# Schema2_bakplan_Lynx.net
KiCad netlist of a schematic drawn in Altium Designer
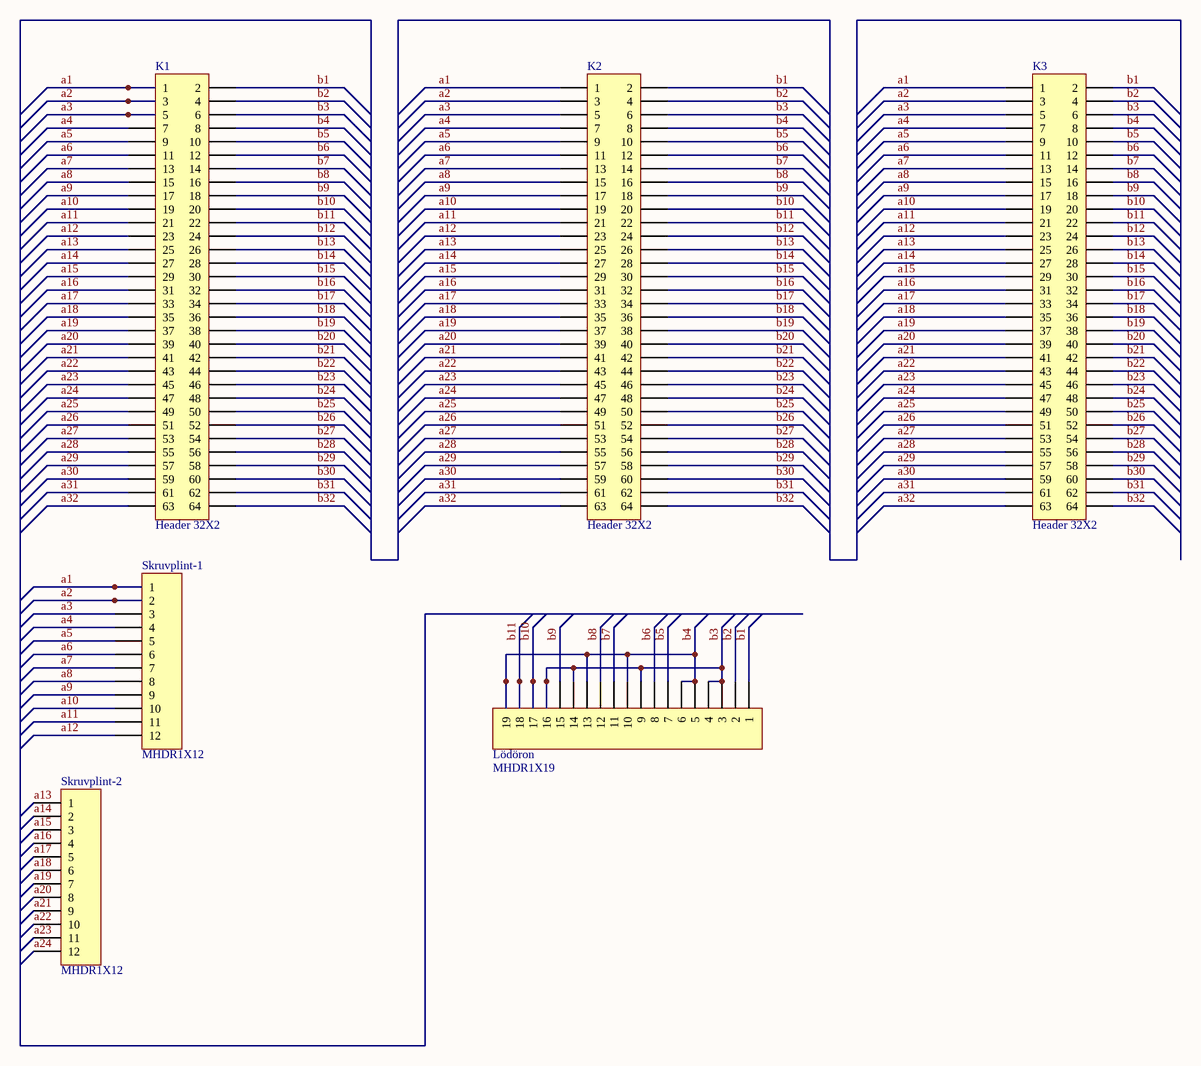
[diagram p0: Schema2_bakplan_Lynx.SchDoc]

(export (version "E")
  (design (tool "Eeschema 10.0.6"))
  (components
    (comp (ref "K1")
      (value "Header 32X2")
      (footprint "DIN41612_EuropadonB64_Hyls")
      (description "Header, 30-Pin, Dual row")
      (fields (field (name "MANUFACTURER") "Generic Components") (field (name "PUBLISHER") "Altium Limited"))
      (libsource (lib "Bakplan_Lynx") (part "Header 30X2"))
    )
    (comp (ref "K2")
      (value "Header 32X2")
      (footprint "DIN41612_EuropadonB64_Hyls")
      (description "Header, 30-Pin, Dual row")
      (fields (field (name "MANUFACTURER") "Generic Components") (field (name "PUBLISHER") "Altium Limited"))
      (libsource (lib "Bakplan_Lynx") (part "Header 30X2"))
    )
    (comp (ref "K3")
      (value "Header 32X2")
      (footprint "DIN41612_EuropadonB64_Hyls")
      (description "Header, 30-Pin, Dual row")
      (fields (field (name "MANUFACTURER") "Generic Components") (field (name "PUBLISHER") "Altium Limited"))
      (libsource (lib "Bakplan_Lynx") (part "Header 30X2"))
    )
    (comp (ref "Lödöron")
      (value "MHDR1X19")
      (footprint "Lödöron_19:Lödöron_19")
      (description "Header, 19-Pin")
      (fields (field (name "MANUFACTURER") "Generic Components") (field (name "PUBLISHER") "Altium Limited"))
      (libsource (lib "Miscellaneous Connectors") (part "MHDR1X19"))
    )
    (comp (ref "Skruvplint-1")
      (value "MHDR1X12")
      (footprint "Plint12:Plint12")
      (description "Header, 12-Pin")
      (fields (field (name "MANUFACTURER") "Generic Components") (field (name "PUBLISHER") "Altium Limited"))
      (libsource (lib "Bakplan_Lynx") (part "MHDR1X12"))
    )
    (comp (ref "Skruvplint-2")
      (value "MHDR1X12")
      (footprint "Plint12:Plint12")
      (description "Header, 12-Pin")
      (fields (field (name "MANUFACTURER") "Generic Components") (field (name "PUBLISHER") "Altium Limited"))
      (libsource (lib "Bakplan_Lynx") (part "MHDR1X12"))
    )
  )
  (nets
    (net (code "1") (name "/a1") (class "Default")
      (node (ref "K1") (pin "1") (pinfunction "1_1") (pintype "passive"))
      (node (ref "K2") (pin "1") (pinfunction "1_1") (pintype "passive"))
      (node (ref "K3") (pin "1") (pinfunction "1_1") (pintype "passive"))
      (node (ref "Skruvplint-1") (pin "1") (pinfunction "1_1") (pintype "passive"))
    )
    (net (code "2") (name "/a2") (class "Default")
      (node (ref "K1") (pin "3") (pinfunction "3_3") (pintype "passive"))
      (node (ref "K2") (pin "3") (pinfunction "3_3") (pintype "passive"))
      (node (ref "K3") (pin "3") (pinfunction "3_3") (pintype "passive"))
      (node (ref "Skruvplint-1") (pin "2") (pinfunction "2_2") (pintype "passive"))
    )
    (net (code "3") (name "/a3") (class "Default")
      (node (ref "K1") (pin "5") (pinfunction "5_5") (pintype "passive"))
      (node (ref "K2") (pin "5") (pinfunction "5_5") (pintype "passive"))
      (node (ref "K3") (pin "5") (pinfunction "5_5") (pintype "passive"))
      (node (ref "Skruvplint-1") (pin "3") (pinfunction "3_3") (pintype "passive"))
    )
    (net (code "4") (name "/a4") (class "Default")
      (node (ref "K1") (pin "7") (pinfunction "7_7") (pintype "passive"))
      (node (ref "K2") (pin "7") (pinfunction "7_7") (pintype "passive"))
      (node (ref "K3") (pin "7") (pinfunction "7_7") (pintype "passive"))
      (node (ref "Skruvplint-1") (pin "4") (pinfunction "4_4") (pintype "passive"))
    )
    (net (code "5") (name "/a5") (class "Default")
      (node (ref "K1") (pin "9") (pinfunction "9_9") (pintype "passive"))
      (node (ref "K2") (pin "9") (pinfunction "9_9") (pintype "passive"))
      (node (ref "K3") (pin "9") (pinfunction "9_9") (pintype "passive"))
      (node (ref "Skruvplint-1") (pin "5") (pinfunction "5_5") (pintype "passive"))
    )
    (net (code "6") (name "/a6") (class "Default")
      (node (ref "K1") (pin "11") (pinfunction "11_11") (pintype "passive"))
      (node (ref "K2") (pin "11") (pinfunction "11_11") (pintype "passive"))
      (node (ref "K3") (pin "11") (pinfunction "11_11") (pintype "passive"))
      (node (ref "Skruvplint-1") (pin "6") (pinfunction "6_6") (pintype "passive"))
    )
    (net (code "7") (name "/a7") (class "Default")
      (node (ref "K1") (pin "13") (pinfunction "13_13") (pintype "passive"))
      (node (ref "K2") (pin "13") (pinfunction "13_13") (pintype "passive"))
      (node (ref "K3") (pin "13") (pinfunction "13_13") (pintype "passive"))
      (node (ref "Skruvplint-1") (pin "7") (pinfunction "7_7") (pintype "passive"))
    )
    (net (code "8") (name "/a8") (class "Default")
      (node (ref "K1") (pin "15") (pinfunction "15_15") (pintype "passive"))
      (node (ref "K2") (pin "15") (pinfunction "15_15") (pintype "passive"))
      (node (ref "K3") (pin "15") (pinfunction "15_15") (pintype "passive"))
      (node (ref "Skruvplint-1") (pin "8") (pinfunction "8_8") (pintype "passive"))
    )
    (net (code "9") (name "/a9") (class "Default")
      (node (ref "K1") (pin "17") (pinfunction "17_17") (pintype "passive"))
      (node (ref "K2") (pin "17") (pinfunction "17_17") (pintype "passive"))
      (node (ref "K3") (pin "17") (pinfunction "17_17") (pintype "passive"))
      (node (ref "Skruvplint-1") (pin "9") (pinfunction "9_9") (pintype "passive"))
    )
    (net (code "10") (name "/a10") (class "Default")
      (node (ref "K1") (pin "19") (pinfunction "19_19") (pintype "passive"))
      (node (ref "K2") (pin "19") (pinfunction "19_19") (pintype "passive"))
      (node (ref "K3") (pin "19") (pinfunction "19_19") (pintype "passive"))
      (node (ref "Skruvplint-1") (pin "10") (pinfunction "10_10") (pintype "passive"))
    )
    (net (code "11") (name "/a11") (class "Default")
      (node (ref "K1") (pin "21") (pinfunction "21_21") (pintype "passive"))
      (node (ref "K2") (pin "21") (pinfunction "21_21") (pintype "passive"))
      (node (ref "K3") (pin "21") (pinfunction "21_21") (pintype "passive"))
      (node (ref "Skruvplint-1") (pin "11") (pinfunction "11_11") (pintype "passive"))
    )
    (net (code "12") (name "/a12") (class "Default")
      (node (ref "K1") (pin "23") (pinfunction "23_23") (pintype "passive"))
      (node (ref "K2") (pin "23") (pinfunction "23_23") (pintype "passive"))
      (node (ref "K3") (pin "23") (pinfunction "23_23") (pintype "passive"))
      (node (ref "Skruvplint-1") (pin "12") (pinfunction "12_12") (pintype "passive"))
    )
    (net (code "13") (name "/a13") (class "Default")
      (node (ref "K1") (pin "25") (pinfunction "25_25") (pintype "passive"))
      (node (ref "K2") (pin "25") (pinfunction "25_25") (pintype "passive"))
      (node (ref "K3") (pin "25") (pinfunction "25_25") (pintype "passive"))
      (node (ref "Skruvplint-2") (pin "1") (pinfunction "1_1") (pintype "passive"))
    )
    (net (code "14") (name "/a14") (class "Default")
      (node (ref "K1") (pin "27") (pinfunction "27_27") (pintype "passive"))
      (node (ref "K2") (pin "27") (pinfunction "27_27") (pintype "passive"))
      (node (ref "K3") (pin "27") (pinfunction "27_27") (pintype "passive"))
      (node (ref "Skruvplint-2") (pin "2") (pinfunction "2_2") (pintype "passive"))
    )
    (net (code "15") (name "/a15") (class "Default")
      (node (ref "K1") (pin "29") (pinfunction "29_29") (pintype "passive"))
      (node (ref "K2") (pin "29") (pinfunction "29_29") (pintype "passive"))
      (node (ref "K3") (pin "29") (pinfunction "29_29") (pintype "passive"))
      (node (ref "Skruvplint-2") (pin "3") (pinfunction "3_3") (pintype "passive"))
    )
    (net (code "16") (name "/a16") (class "Default")
      (node (ref "K1") (pin "31") (pinfunction "31_31") (pintype "passive"))
      (node (ref "K2") (pin "31") (pinfunction "31_31") (pintype "passive"))
      (node (ref "K3") (pin "31") (pinfunction "31_31") (pintype "passive"))
      (node (ref "Skruvplint-2") (pin "4") (pinfunction "4_4") (pintype "passive"))
    )
    (net (code "17") (name "/a17") (class "Default")
      (node (ref "K1") (pin "33") (pinfunction "33_33") (pintype "passive"))
      (node (ref "K2") (pin "33") (pinfunction "33_33") (pintype "passive"))
      (node (ref "K3") (pin "33") (pinfunction "33_33") (pintype "passive"))
      (node (ref "Skruvplint-2") (pin "5") (pinfunction "5_5") (pintype "passive"))
    )
    (net (code "18") (name "/a18") (class "Default")
      (node (ref "K1") (pin "35") (pinfunction "35_35") (pintype "passive"))
      (node (ref "K2") (pin "35") (pinfunction "35_35") (pintype "passive"))
      (node (ref "K3") (pin "35") (pinfunction "35_35") (pintype "passive"))
      (node (ref "Skruvplint-2") (pin "6") (pinfunction "6_6") (pintype "passive"))
    )
    (net (code "19") (name "/a19") (class "Default")
      (node (ref "K1") (pin "37") (pinfunction "37_37") (pintype "passive"))
      (node (ref "K2") (pin "37") (pinfunction "37_37") (pintype "passive"))
      (node (ref "K3") (pin "37") (pinfunction "37_37") (pintype "passive"))
      (node (ref "Skruvplint-2") (pin "7") (pinfunction "7_7") (pintype "passive"))
    )
    (net (code "20") (name "/a20") (class "Default")
      (node (ref "K1") (pin "39") (pinfunction "39_39") (pintype "passive"))
      (node (ref "K2") (pin "39") (pinfunction "39_39") (pintype "passive"))
      (node (ref "K3") (pin "39") (pinfunction "39_39") (pintype "passive"))
      (node (ref "Skruvplint-2") (pin "8") (pinfunction "8_8") (pintype "passive"))
    )
    (net (code "21") (name "/a21") (class "Default")
      (node (ref "K1") (pin "41") (pinfunction "41_41") (pintype "passive"))
      (node (ref "K2") (pin "41") (pinfunction "41_41") (pintype "passive"))
      (node (ref "K3") (pin "41") (pinfunction "41_41") (pintype "passive"))
      (node (ref "Skruvplint-2") (pin "9") (pinfunction "9_9") (pintype "passive"))
    )
    (net (code "22") (name "/a22") (class "Default")
      (node (ref "K1") (pin "43") (pinfunction "43_43") (pintype "passive"))
      (node (ref "K2") (pin "43") (pinfunction "43_43") (pintype "passive"))
      (node (ref "K3") (pin "43") (pinfunction "43_43") (pintype "passive"))
      (node (ref "Skruvplint-2") (pin "10") (pinfunction "10_10") (pintype "passive"))
    )
    (net (code "23") (name "/a23") (class "Default")
      (node (ref "K1") (pin "45") (pinfunction "45_45") (pintype "passive"))
      (node (ref "K2") (pin "45") (pinfunction "45_45") (pintype "passive"))
      (node (ref "K3") (pin "45") (pinfunction "45_45") (pintype "passive"))
      (node (ref "Skruvplint-2") (pin "11") (pinfunction "11_11") (pintype "passive"))
    )
    (net (code "24") (name "/a24") (class "Default")
      (node (ref "K1") (pin "47") (pinfunction "47_47") (pintype "passive"))
      (node (ref "K2") (pin "47") (pinfunction "47_47") (pintype "passive"))
      (node (ref "K3") (pin "47") (pinfunction "47_47") (pintype "passive"))
      (node (ref "Skruvplint-2") (pin "12") (pinfunction "12_12") (pintype "passive"))
    )
    (net (code "25") (name "/a25") (class "Default")
      (node (ref "K1") (pin "49") (pinfunction "49_49") (pintype "passive"))
      (node (ref "K2") (pin "49") (pinfunction "49_49") (pintype "passive"))
      (node (ref "K3") (pin "49") (pinfunction "49_49") (pintype "passive"))
    )
    (net (code "26") (name "/a26") (class "Default")
      (node (ref "K1") (pin "51") (pinfunction "51_51") (pintype "passive"))
      (node (ref "K2") (pin "51") (pinfunction "51_51") (pintype "passive"))
      (node (ref "K3") (pin "51") (pinfunction "51_51") (pintype "passive"))
    )
    (net (code "27") (name "/a27") (class "Default")
      (node (ref "K1") (pin "53") (pinfunction "53_53") (pintype "passive"))
      (node (ref "K2") (pin "53") (pinfunction "53_53") (pintype "passive"))
      (node (ref "K3") (pin "53") (pinfunction "53_53") (pintype "passive"))
    )
    (net (code "28") (name "/a28") (class "Default")
      (node (ref "K1") (pin "55") (pinfunction "55_55") (pintype "passive"))
      (node (ref "K2") (pin "55") (pinfunction "55_55") (pintype "passive"))
      (node (ref "K3") (pin "55") (pinfunction "55_55") (pintype "passive"))
    )
    (net (code "29") (name "/a29") (class "Default")
      (node (ref "K1") (pin "57") (pinfunction "57_57") (pintype "passive"))
      (node (ref "K2") (pin "57") (pinfunction "57_57") (pintype "passive"))
      (node (ref "K3") (pin "57") (pinfunction "57_57") (pintype "passive"))
    )
    (net (code "30") (name "/a30") (class "Default")
      (node (ref "K1") (pin "59") (pinfunction "59_59") (pintype "passive"))
      (node (ref "K2") (pin "59") (pinfunction "59_59") (pintype "passive"))
      (node (ref "K3") (pin "59") (pinfunction "59_59") (pintype "passive"))
    )
    (net (code "31") (name "/a31") (class "Default")
      (node (ref "K1") (pin "61") (pinfunction "61_61") (pintype "passive"))
      (node (ref "K2") (pin "61") (pinfunction "61_61") (pintype "passive"))
      (node (ref "K3") (pin "61") (pinfunction "61_61") (pintype "passive"))
    )
    (net (code "32") (name "/a32") (class "Default")
      (node (ref "K1") (pin "63") (pinfunction "63_63") (pintype "passive"))
      (node (ref "K2") (pin "63") (pinfunction "63_63") (pintype "passive"))
      (node (ref "K3") (pin "63") (pinfunction "63_63") (pintype "passive"))
    )
    (net (code "33") (name "/b1") (class "Default")
      (node (ref "K1") (pin "2") (pinfunction "2_2") (pintype "passive"))
      (node (ref "K2") (pin "2") (pinfunction "2_2") (pintype "passive"))
      (node (ref "K3") (pin "2") (pinfunction "2_2") (pintype "passive"))
      (node (ref "Lödöron") (pin "1") (pinfunction "1_1") (pintype "passive"))
    )
    (net (code "34") (name "/b2") (class "Default")
      (node (ref "K1") (pin "4") (pinfunction "4_4") (pintype "passive"))
      (node (ref "K2") (pin "4") (pinfunction "4_4") (pintype "passive"))
      (node (ref "K3") (pin "4") (pinfunction "4_4") (pintype "passive"))
      (node (ref "Lödöron") (pin "2") (pinfunction "2_2") (pintype "passive"))
    )
    (net (code "35") (name "/b3") (class "Default")
      (node (ref "K1") (pin "6") (pinfunction "6_6") (pintype "passive"))
      (node (ref "K2") (pin "6") (pinfunction "6_6") (pintype "passive"))
      (node (ref "K3") (pin "6") (pinfunction "6_6") (pintype "passive"))
      (node (ref "Lödöron") (pin "14") (pinfunction "14_14") (pintype "passive"))
      (node (ref "Lödöron") (pin "16") (pinfunction "16_16") (pintype "passive"))
      (node (ref "Lödöron") (pin "3") (pinfunction "3_3") (pintype "passive"))
      (node (ref "Lödöron") (pin "4") (pinfunction "4_4") (pintype "passive"))
      (node (ref "Lödöron") (pin "9") (pinfunction "9_9") (pintype "passive"))
    )
    (net (code "36") (name "/b4") (class "Default")
      (node (ref "K1") (pin "8") (pinfunction "8_8") (pintype "passive"))
      (node (ref "K2") (pin "8") (pinfunction "8_8") (pintype "passive"))
      (node (ref "K3") (pin "8") (pinfunction "8_8") (pintype "passive"))
      (node (ref "Lödöron") (pin "10") (pinfunction "10_10") (pintype "passive"))
      (node (ref "Lödöron") (pin "13") (pinfunction "13_13") (pintype "passive"))
      (node (ref "Lödöron") (pin "19") (pinfunction "19_19") (pintype "passive"))
      (node (ref "Lödöron") (pin "5") (pinfunction "5_5") (pintype "passive"))
      (node (ref "Lödöron") (pin "6") (pinfunction "6_6") (pintype "passive"))
    )
    (net (code "37") (name "/b5") (class "Default")
      (node (ref "K1") (pin "10") (pinfunction "10_10") (pintype "passive"))
      (node (ref "K2") (pin "10") (pinfunction "10_10") (pintype "passive"))
      (node (ref "K3") (pin "10") (pinfunction "10_10") (pintype "passive"))
      (node (ref "Lödöron") (pin "7") (pinfunction "7_7") (pintype "passive"))
    )
    (net (code "38") (name "/b6") (class "Default")
      (node (ref "K1") (pin "12") (pinfunction "12_12") (pintype "passive"))
      (node (ref "K2") (pin "12") (pinfunction "12_12") (pintype "passive"))
      (node (ref "K3") (pin "12") (pinfunction "12_12") (pintype "passive"))
      (node (ref "Lödöron") (pin "8") (pinfunction "8_8") (pintype "passive"))
    )
    (net (code "39") (name "/b7") (class "Default")
      (node (ref "K1") (pin "14") (pinfunction "14_14") (pintype "passive"))
      (node (ref "K2") (pin "14") (pinfunction "14_14") (pintype "passive"))
      (node (ref "K3") (pin "14") (pinfunction "14_14") (pintype "passive"))
      (node (ref "Lödöron") (pin "11") (pinfunction "11_11") (pintype "passive"))
    )
    (net (code "40") (name "/b8") (class "Default")
      (node (ref "K1") (pin "16") (pinfunction "16_16") (pintype "passive"))
      (node (ref "K2") (pin "16") (pinfunction "16_16") (pintype "passive"))
      (node (ref "K3") (pin "16") (pinfunction "16_16") (pintype "passive"))
      (node (ref "Lödöron") (pin "12") (pinfunction "12_12") (pintype "passive"))
    )
    (net (code "41") (name "/b9") (class "Default")
      (node (ref "K1") (pin "18") (pinfunction "18_18") (pintype "passive"))
      (node (ref "K2") (pin "18") (pinfunction "18_18") (pintype "passive"))
      (node (ref "K3") (pin "18") (pinfunction "18_18") (pintype "passive"))
      (node (ref "Lödöron") (pin "15") (pinfunction "15_15") (pintype "passive"))
    )
    (net (code "42") (name "/b10") (class "Default")
      (node (ref "K1") (pin "20") (pinfunction "20_20") (pintype "passive"))
      (node (ref "K2") (pin "20") (pinfunction "20_20") (pintype "passive"))
      (node (ref "K3") (pin "20") (pinfunction "20_20") (pintype "passive"))
      (node (ref "Lödöron") (pin "17") (pinfunction "17_17") (pintype "passive"))
    )
    (net (code "43") (name "/b11") (class "Default")
      (node (ref "K1") (pin "22") (pinfunction "22_22") (pintype "passive"))
      (node (ref "K2") (pin "22") (pinfunction "22_22") (pintype "passive"))
      (node (ref "K3") (pin "22") (pinfunction "22_22") (pintype "passive"))
      (node (ref "Lödöron") (pin "18") (pinfunction "18_18") (pintype "passive"))
    )
    (net (code "44") (name "/b12") (class "Default")
      (node (ref "K1") (pin "24") (pinfunction "24_24") (pintype "passive"))
      (node (ref "K2") (pin "24") (pinfunction "24_24") (pintype "passive"))
      (node (ref "K3") (pin "24") (pinfunction "24_24") (pintype "passive"))
    )
    (net (code "45") (name "/b13") (class "Default")
      (node (ref "K1") (pin "26") (pinfunction "26_26") (pintype "passive"))
      (node (ref "K2") (pin "26") (pinfunction "26_26") (pintype "passive"))
      (node (ref "K3") (pin "26") (pinfunction "26_26") (pintype "passive"))
    )
    (net (code "46") (name "/b14") (class "Default")
      (node (ref "K1") (pin "28") (pinfunction "28_28") (pintype "passive"))
      (node (ref "K2") (pin "28") (pinfunction "28_28") (pintype "passive"))
      (node (ref "K3") (pin "28") (pinfunction "28_28") (pintype "passive"))
    )
    (net (code "47") (name "/b15") (class "Default")
      (node (ref "K1") (pin "30") (pinfunction "30_30") (pintype "passive"))
      (node (ref "K2") (pin "30") (pinfunction "30_30") (pintype "passive"))
      (node (ref "K3") (pin "30") (pinfunction "30_30") (pintype "passive"))
    )
    (net (code "48") (name "/b16") (class "Default")
      (node (ref "K1") (pin "32") (pinfunction "32_32") (pintype "passive"))
      (node (ref "K2") (pin "32") (pinfunction "32_32") (pintype "passive"))
      (node (ref "K3") (pin "32") (pinfunction "32_32") (pintype "passive"))
    )
    (net (code "49") (name "/b17") (class "Default")
      (node (ref "K1") (pin "34") (pinfunction "34_34") (pintype "passive"))
      (node (ref "K2") (pin "34") (pinfunction "34_34") (pintype "passive"))
      (node (ref "K3") (pin "34") (pinfunction "34_34") (pintype "passive"))
    )
    (net (code "50") (name "/b18") (class "Default")
      (node (ref "K1") (pin "36") (pinfunction "36_36") (pintype "passive"))
      (node (ref "K2") (pin "36") (pinfunction "36_36") (pintype "passive"))
      (node (ref "K3") (pin "36") (pinfunction "36_36") (pintype "passive"))
    )
    (net (code "51") (name "/b19") (class "Default")
      (node (ref "K1") (pin "38") (pinfunction "38_38") (pintype "passive"))
      (node (ref "K2") (pin "38") (pinfunction "38_38") (pintype "passive"))
      (node (ref "K3") (pin "38") (pinfunction "38_38") (pintype "passive"))
    )
    (net (code "52") (name "/b20") (class "Default")
      (node (ref "K1") (pin "40") (pinfunction "40_40") (pintype "passive"))
      (node (ref "K2") (pin "40") (pinfunction "40_40") (pintype "passive"))
      (node (ref "K3") (pin "40") (pinfunction "40_40") (pintype "passive"))
    )
    (net (code "53") (name "/b21") (class "Default")
      (node (ref "K1") (pin "42") (pinfunction "42_42") (pintype "passive"))
      (node (ref "K2") (pin "42") (pinfunction "42_42") (pintype "passive"))
      (node (ref "K3") (pin "42") (pinfunction "42_42") (pintype "passive"))
    )
    (net (code "54") (name "/b22") (class "Default")
      (node (ref "K1") (pin "44") (pinfunction "44_44") (pintype "passive"))
      (node (ref "K2") (pin "44") (pinfunction "44_44") (pintype "passive"))
      (node (ref "K3") (pin "44") (pinfunction "44_44") (pintype "passive"))
    )
    (net (code "55") (name "/b23") (class "Default")
      (node (ref "K1") (pin "46") (pinfunction "46_46") (pintype "passive"))
      (node (ref "K2") (pin "46") (pinfunction "46_46") (pintype "passive"))
      (node (ref "K3") (pin "46") (pinfunction "46_46") (pintype "passive"))
    )
    (net (code "56") (name "/b24") (class "Default")
      (node (ref "K1") (pin "48") (pinfunction "48_48") (pintype "passive"))
      (node (ref "K2") (pin "48") (pinfunction "48_48") (pintype "passive"))
      (node (ref "K3") (pin "48") (pinfunction "48_48") (pintype "passive"))
    )
    (net (code "57") (name "/b25") (class "Default")
      (node (ref "K1") (pin "50") (pinfunction "50_50") (pintype "passive"))
      (node (ref "K2") (pin "50") (pinfunction "50_50") (pintype "passive"))
      (node (ref "K3") (pin "50") (pinfunction "50_50") (pintype "passive"))
    )
    (net (code "58") (name "/b26") (class "Default")
      (node (ref "K1") (pin "52") (pinfunction "52_52") (pintype "passive"))
      (node (ref "K2") (pin "52") (pinfunction "52_52") (pintype "passive"))
      (node (ref "K3") (pin "52") (pinfunction "52_52") (pintype "passive"))
    )
    (net (code "59") (name "/b27") (class "Default")
      (node (ref "K1") (pin "54") (pinfunction "54_54") (pintype "passive"))
      (node (ref "K2") (pin "54") (pinfunction "54_54") (pintype "passive"))
      (node (ref "K3") (pin "54") (pinfunction "54_54") (pintype "passive"))
    )
    (net (code "60") (name "/b28") (class "Default")
      (node (ref "K1") (pin "56") (pinfunction "56_56") (pintype "passive"))
      (node (ref "K2") (pin "56") (pinfunction "56_56") (pintype "passive"))
      (node (ref "K3") (pin "56") (pinfunction "56_56") (pintype "passive"))
    )
    (net (code "61") (name "/b29") (class "Default")
      (node (ref "K1") (pin "58") (pinfunction "58_58") (pintype "passive"))
      (node (ref "K2") (pin "58") (pinfunction "58_58") (pintype "passive"))
      (node (ref "K3") (pin "58") (pinfunction "58_58") (pintype "passive"))
    )
    (net (code "62") (name "/b30") (class "Default")
      (node (ref "K1") (pin "60") (pinfunction "60_60") (pintype "passive"))
      (node (ref "K2") (pin "60") (pinfunction "60_60") (pintype "passive"))
      (node (ref "K3") (pin "60") (pinfunction "60_60") (pintype "passive"))
    )
    (net (code "63") (name "/b31") (class "Default")
      (node (ref "K1") (pin "62") (pinfunction "62_62") (pintype "passive"))
      (node (ref "K2") (pin "62") (pinfunction "62_62") (pintype "passive"))
      (node (ref "K3") (pin "62") (pinfunction "62_62") (pintype "passive"))
    )
    (net (code "64") (name "/b32") (class "Default")
      (node (ref "K1") (pin "64") (pinfunction "64_64") (pintype "passive"))
      (node (ref "K2") (pin "64") (pinfunction "64_64") (pintype "passive"))
      (node (ref "K3") (pin "64") (pinfunction "64_64") (pintype "passive"))
    )
  )
)
